# HDMI.net
KiCad netlist of a schematic drawn in Altium Designer
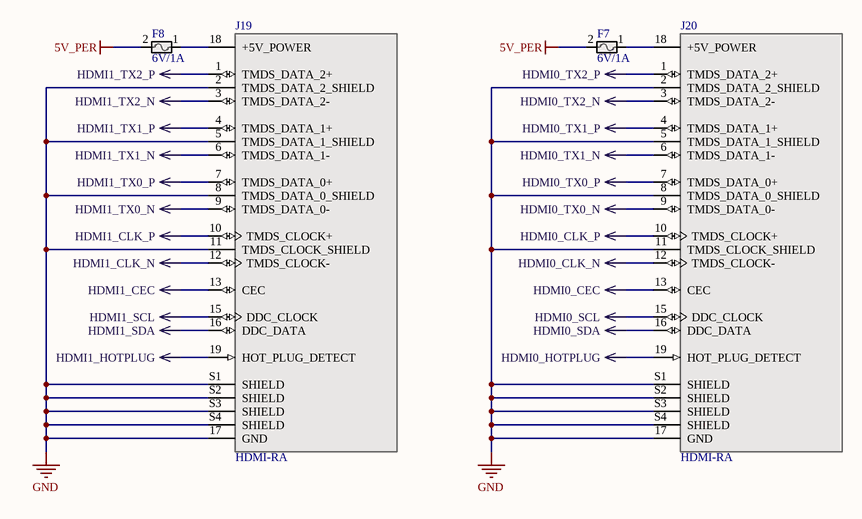
[diagram p0: HDMI.SchDoc]

(export (version "E")
  (design (tool "Eeschema 10.0.6"))
  (components
    (comp (ref "F7")
      (value "6V/1A")
      (footprint "0805")
      (description "Polymeric PTC Resettable Fuse 6V 1 A Ih Surface Mount 0805 (2012 Metric), Concave")
      (fields (field (name "MANUFACTURER") "Bel") (field (name "MANUFACTURER PART NUMBER") "0ZCK0100FF2E"))
      (libsource (lib "Regulators") (part "0ZCK0100FF2E"))
    )
    (comp (ref "F8")
      (value "6V/1A")
      (footprint "0805")
      (description "Polymeric PTC Resettable Fuse 6V 1 A Ih Surface Mount 0805 (2012 Metric), Concave")
      (fields (field (name "MANUFACTURER") "Bel") (field (name "MANUFACTURER PART NUMBER") "0ZCK0100FF2E"))
      (libsource (lib "Regulators") (part "0ZCK0100FF2E"))
    )
    (comp (ref "J19")
      (value "HDMI-RA")
      (footprint "CUI_HD01-19-RA-TH")
      (description "HDMI 2.1, Receptacle Connector, 19 Position, Through Hole, Vertical, Right Angle, Tray Packaging")
      (fields (field (name "MF") "CUI Devices") (field (name "DIGI-KEY_PART_NUMBER") "2223-HD01-19-RA-TH-ND"))
      (libsource (lib "Connectors") (part "HD01-19-RA-TH"))
    )
    (comp (ref "J20")
      (value "HDMI-RA")
      (footprint "CUI_HD01-19-RA-TH")
      (description "HDMI 2.1, Receptacle Connector, 19 Position, Through Hole, Vertical, Right Angle, Tray Packaging")
      (fields (field (name "MF") "CUI Devices") (field (name "DIGI-KEY_PART_NUMBER") "2223-HD01-19-RA-TH-ND"))
      (libsource (lib "Connectors") (part "HD01-19-RA-TH"))
    )
  )
  (nets
    (net (code "1") (name "5V_PER") (class "Default")
      (node (ref "F7") (pin "2") (pinfunction "2_2") (pintype "passive"))
      (node (ref "F8") (pin "2") (pinfunction "2_2") (pintype "passive"))
    )
    (net (code "2") (name "GND") (class "Default")
      (node (ref "J19") (pin "11") (pinfunction "TMDS_CLOCK_SHIELD_11") (pintype "passive"))
      (node (ref "J19") (pin "17") (pinfunction "GND_17") (pintype "power_in"))
      (node (ref "J19") (pin "2") (pinfunction "TMDS_DATA_2_SHIELD_2") (pintype "passive"))
      (node (ref "J19") (pin "5") (pinfunction "TMDS_DATA_1_SHIELD_5") (pintype "passive"))
      (node (ref "J19") (pin "8") (pinfunction "TMDS_DATA_0_SHIELD_8") (pintype "passive"))
      (node (ref "J19") (pin "S1") (pinfunction "SHIELD_S1") (pintype "passive"))
      (node (ref "J19") (pin "S2") (pinfunction "SHIELD_S2") (pintype "passive"))
      (node (ref "J19") (pin "S3") (pinfunction "SHIELD_S3") (pintype "passive"))
      (node (ref "J19") (pin "S4") (pinfunction "SHIELD_S4") (pintype "passive"))
      (node (ref "J20") (pin "11") (pinfunction "TMDS_CLOCK_SHIELD_11") (pintype "passive"))
      (node (ref "J20") (pin "17") (pinfunction "GND_17") (pintype "power_in"))
      (node (ref "J20") (pin "2") (pinfunction "TMDS_DATA_2_SHIELD_2") (pintype "passive"))
      (node (ref "J20") (pin "5") (pinfunction "TMDS_DATA_1_SHIELD_5") (pintype "passive"))
      (node (ref "J20") (pin "8") (pinfunction "TMDS_DATA_0_SHIELD_8") (pintype "passive"))
      (node (ref "J20") (pin "S1") (pinfunction "SHIELD_S1") (pintype "passive"))
      (node (ref "J20") (pin "S2") (pinfunction "SHIELD_S2") (pintype "passive"))
      (node (ref "J20") (pin "S3") (pinfunction "SHIELD_S3") (pintype "passive"))
      (node (ref "J20") (pin "S4") (pinfunction "SHIELD_S4") (pintype "passive"))
    )
    (net (code "3") (name "HDMI0_CEC") (class "Default")
      (node (ref "J20") (pin "13") (pinfunction "CEC_13") (pintype "bidirectional"))
    )
    (net (code "4") (name "HDMI0_CLK_N") (class "Default")
      (node (ref "J20") (pin "12") (pinfunction "TMDS_CLOCK-_12") (pintype "bidirectional"))
    )
    (net (code "5") (name "HDMI0_CLK_P") (class "Default")
      (node (ref "J20") (pin "10") (pinfunction "TMDS_CLOCK+_10") (pintype "bidirectional"))
    )
    (net (code "6") (name "HDMI0_HOTPLUG") (class "Default")
      (node (ref "J20") (pin "19") (pinfunction "HOT_PLUG_DETECT_19") (pintype "input"))
    )
    (net (code "7") (name "HDMI0_SCL") (class "Default")
      (node (ref "J20") (pin "15") (pinfunction "DDC_CLOCK_15") (pintype "bidirectional"))
    )
    (net (code "8") (name "HDMI0_SDA") (class "Default")
      (node (ref "J20") (pin "16") (pinfunction "DDC_DATA_16") (pintype "bidirectional"))
    )
    (net (code "9") (name "HDMI0_TX0_N") (class "Default")
      (node (ref "J20") (pin "9") (pinfunction "TMDS_DATA_0-_9") (pintype "bidirectional"))
    )
    (net (code "10") (name "HDMI0_TX0_P") (class "Default")
      (node (ref "J20") (pin "7") (pinfunction "TMDS_DATA_0+_7") (pintype "bidirectional"))
    )
    (net (code "11") (name "HDMI0_TX1_N") (class "Default")
      (node (ref "J20") (pin "6") (pinfunction "TMDS_DATA_1-_6") (pintype "bidirectional"))
    )
    (net (code "12") (name "HDMI0_TX1_P") (class "Default")
      (node (ref "J20") (pin "4") (pinfunction "TMDS_DATA_1+_4") (pintype "bidirectional"))
    )
    (net (code "13") (name "HDMI0_TX2_N") (class "Default")
      (node (ref "J20") (pin "3") (pinfunction "TMDS_DATA_2-_3") (pintype "bidirectional"))
    )
    (net (code "14") (name "HDMI0_TX2_P") (class "Default")
      (node (ref "J20") (pin "1") (pinfunction "TMDS_DATA_2+_1") (pintype "bidirectional"))
    )
    (net (code "15") (name "HDMI1_CEC") (class "Default")
      (node (ref "J19") (pin "13") (pinfunction "CEC_13") (pintype "bidirectional"))
    )
    (net (code "16") (name "HDMI1_CLK_N") (class "Default")
      (node (ref "J19") (pin "12") (pinfunction "TMDS_CLOCK-_12") (pintype "bidirectional"))
    )
    (net (code "17") (name "HDMI1_CLK_P") (class "Default")
      (node (ref "J19") (pin "10") (pinfunction "TMDS_CLOCK+_10") (pintype "bidirectional"))
    )
    (net (code "18") (name "HDMI1_HOTPLUG") (class "Default")
      (node (ref "J19") (pin "19") (pinfunction "HOT_PLUG_DETECT_19") (pintype "input"))
    )
    (net (code "19") (name "HDMI1_SCL") (class "Default")
      (node (ref "J19") (pin "15") (pinfunction "DDC_CLOCK_15") (pintype "bidirectional"))
    )
    (net (code "20") (name "HDMI1_SDA") (class "Default")
      (node (ref "J19") (pin "16") (pinfunction "DDC_DATA_16") (pintype "bidirectional"))
    )
    (net (code "21") (name "HDMI1_TX0_N") (class "Default")
      (node (ref "J19") (pin "9") (pinfunction "TMDS_DATA_0-_9") (pintype "bidirectional"))
    )
    (net (code "22") (name "HDMI1_TX0_P") (class "Default")
      (node (ref "J19") (pin "7") (pinfunction "TMDS_DATA_0+_7") (pintype "bidirectional"))
    )
    (net (code "23") (name "HDMI1_TX1_N") (class "Default")
      (node (ref "J19") (pin "6") (pinfunction "TMDS_DATA_1-_6") (pintype "bidirectional"))
    )
    (net (code "24") (name "HDMI1_TX1_P") (class "Default")
      (node (ref "J19") (pin "4") (pinfunction "TMDS_DATA_1+_4") (pintype "bidirectional"))
    )
    (net (code "25") (name "HDMI1_TX2_N") (class "Default")
      (node (ref "J19") (pin "3") (pinfunction "TMDS_DATA_2-_3") (pintype "bidirectional"))
    )
    (net (code "26") (name "HDMI1_TX2_P") (class "Default")
      (node (ref "J19") (pin "1") (pinfunction "TMDS_DATA_2+_1") (pintype "bidirectional"))
    )
    (net (code "27") (name "Net-(J19-+5V_POWER)") (class "Default")
      (node (ref "F8") (pin "1") (pinfunction "1_1") (pintype "passive"))
      (node (ref "J19") (pin "18") (pinfunction "+5V_POWER_18") (pintype "power_in"))
    )
    (net (code "28") (name "Net-(J20-+5V_POWER)") (class "Default")
      (node (ref "F7") (pin "1") (pinfunction "1_1") (pintype "passive"))
      (node (ref "J20") (pin "18") (pinfunction "+5V_POWER_18") (pintype "power_in"))
    )
  )
)
